# pcb.net
KiCad netlist of a schematic drawn in EasyEDA Pro
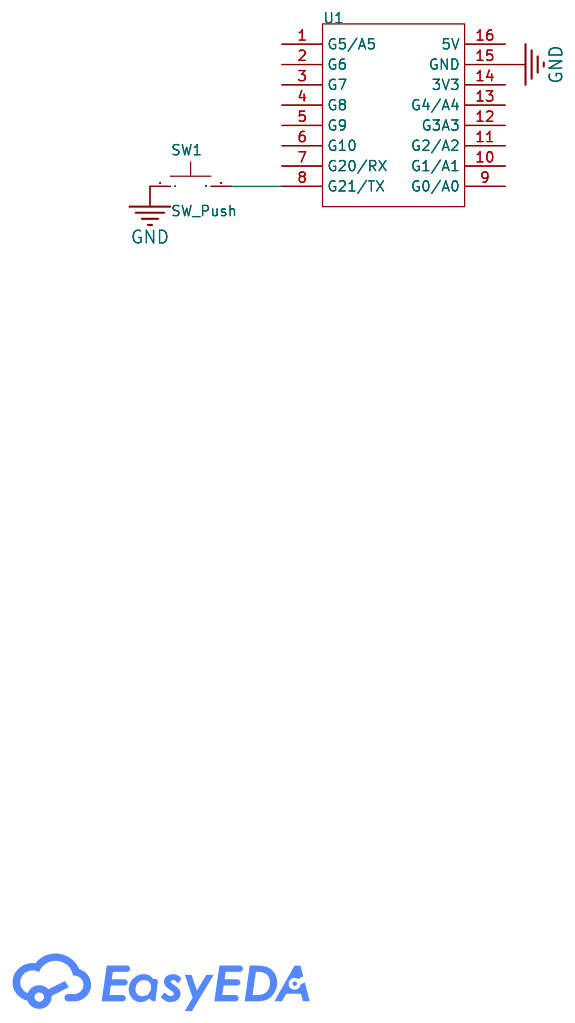
[diagram p0: schematic sheet]

(export (version "E")
  (design (tool "Eeschema 10.0.6"))
  (components
    (comp (ref "SW1")
      (value "SW_Push")
      (footprint "easyedapro:0805")
      (libsource (lib "easyedapro") (part "SW_Push"))
    )
    (comp (ref "U1")
      (value "~")
      (footprint "easyedapro:ESP32 C3 SUPER MINI")
      (libsource (lib "easyedapro") (part "ESP32 C3 SUPER MINI"))
    )
  )
  (nets
    (net (code "1") (name "GND") (class "Default")
      (node (ref "SW1") (pin "1") (pinfunction "1_1") (pintype "input"))
      (node (ref "U1") (pin "15") (pinfunction "GND_15") (pintype "input"))
    )
    (net (code "2") (name "Net-(U1-G21{slash}TX)") (class "Default")
      (node (ref "SW1") (pin "2") (pinfunction "2_2") (pintype "input"))
      (node (ref "U1") (pin "8") (pinfunction "G21/TX_8") (pintype "input"))
    )
    (net (code "3") (name "unconnected-(U1-3V3-Pad14)") (class "Default")
      (node (ref "U1") (pin "14") (pinfunction "3V3_14") (pintype "input"))
    )
    (net (code "4") (name "unconnected-(U1-5V-Pad16)") (class "Default")
      (node (ref "U1") (pin "16") (pinfunction "5V_16") (pintype "input"))
    )
    (net (code "5") (name "unconnected-(U1-G0{slash}A0-Pad9)") (class "Default")
      (node (ref "U1") (pin "9") (pinfunction "G0/A0_9") (pintype "input"))
    )
    (net (code "6") (name "unconnected-(U1-G1{slash}A1-Pad10)") (class "Default")
      (node (ref "U1") (pin "10") (pinfunction "G1/A1_10") (pintype "input"))
    )
    (net (code "7") (name "unconnected-(U1-G2{slash}A2-Pad11)") (class "Default")
      (node (ref "U1") (pin "11") (pinfunction "G2/A2_11") (pintype "input"))
    )
    (net (code "8") (name "unconnected-(U1-G3A3-Pad12)") (class "Default")
      (node (ref "U1") (pin "12") (pinfunction "G3A3_12") (pintype "input"))
    )
    (net (code "9") (name "unconnected-(U1-G4{slash}A4-Pad13)") (class "Default")
      (node (ref "U1") (pin "13") (pinfunction "G4/A4_13") (pintype "input"))
    )
    (net (code "10") (name "unconnected-(U1-G5{slash}A5-Pad1)") (class "Default")
      (node (ref "U1") (pin "1") (pinfunction "G5/A5_1") (pintype "input"))
    )
    (net (code "11") (name "unconnected-(U1-G6-Pad2)") (class "Default")
      (node (ref "U1") (pin "2") (pinfunction "G6_2") (pintype "input"))
    )
    (net (code "12") (name "unconnected-(U1-G7-Pad3)") (class "Default")
      (node (ref "U1") (pin "3") (pinfunction "G7_3") (pintype "input"))
    )
    (net (code "13") (name "unconnected-(U1-G8-Pad4)") (class "Default")
      (node (ref "U1") (pin "4") (pinfunction "G8_4") (pintype "input"))
    )
    (net (code "14") (name "unconnected-(U1-G9-Pad5)") (class "Default")
      (node (ref "U1") (pin "5") (pinfunction "G9_5") (pintype "input"))
    )
    (net (code "15") (name "unconnected-(U1-G10-Pad6)") (class "Default")
      (node (ref "U1") (pin "6") (pinfunction "G10_6") (pintype "input"))
    )
    (net (code "16") (name "unconnected-(U1-G20{slash}RX-Pad7)") (class "Default")
      (node (ref "U1") (pin "7") (pinfunction "G20/RX_7") (pintype "input"))
    )
  )
)
